# motherboard_motor_mcu.net
KiCad netlist of a schematic drawn in Altium Designer
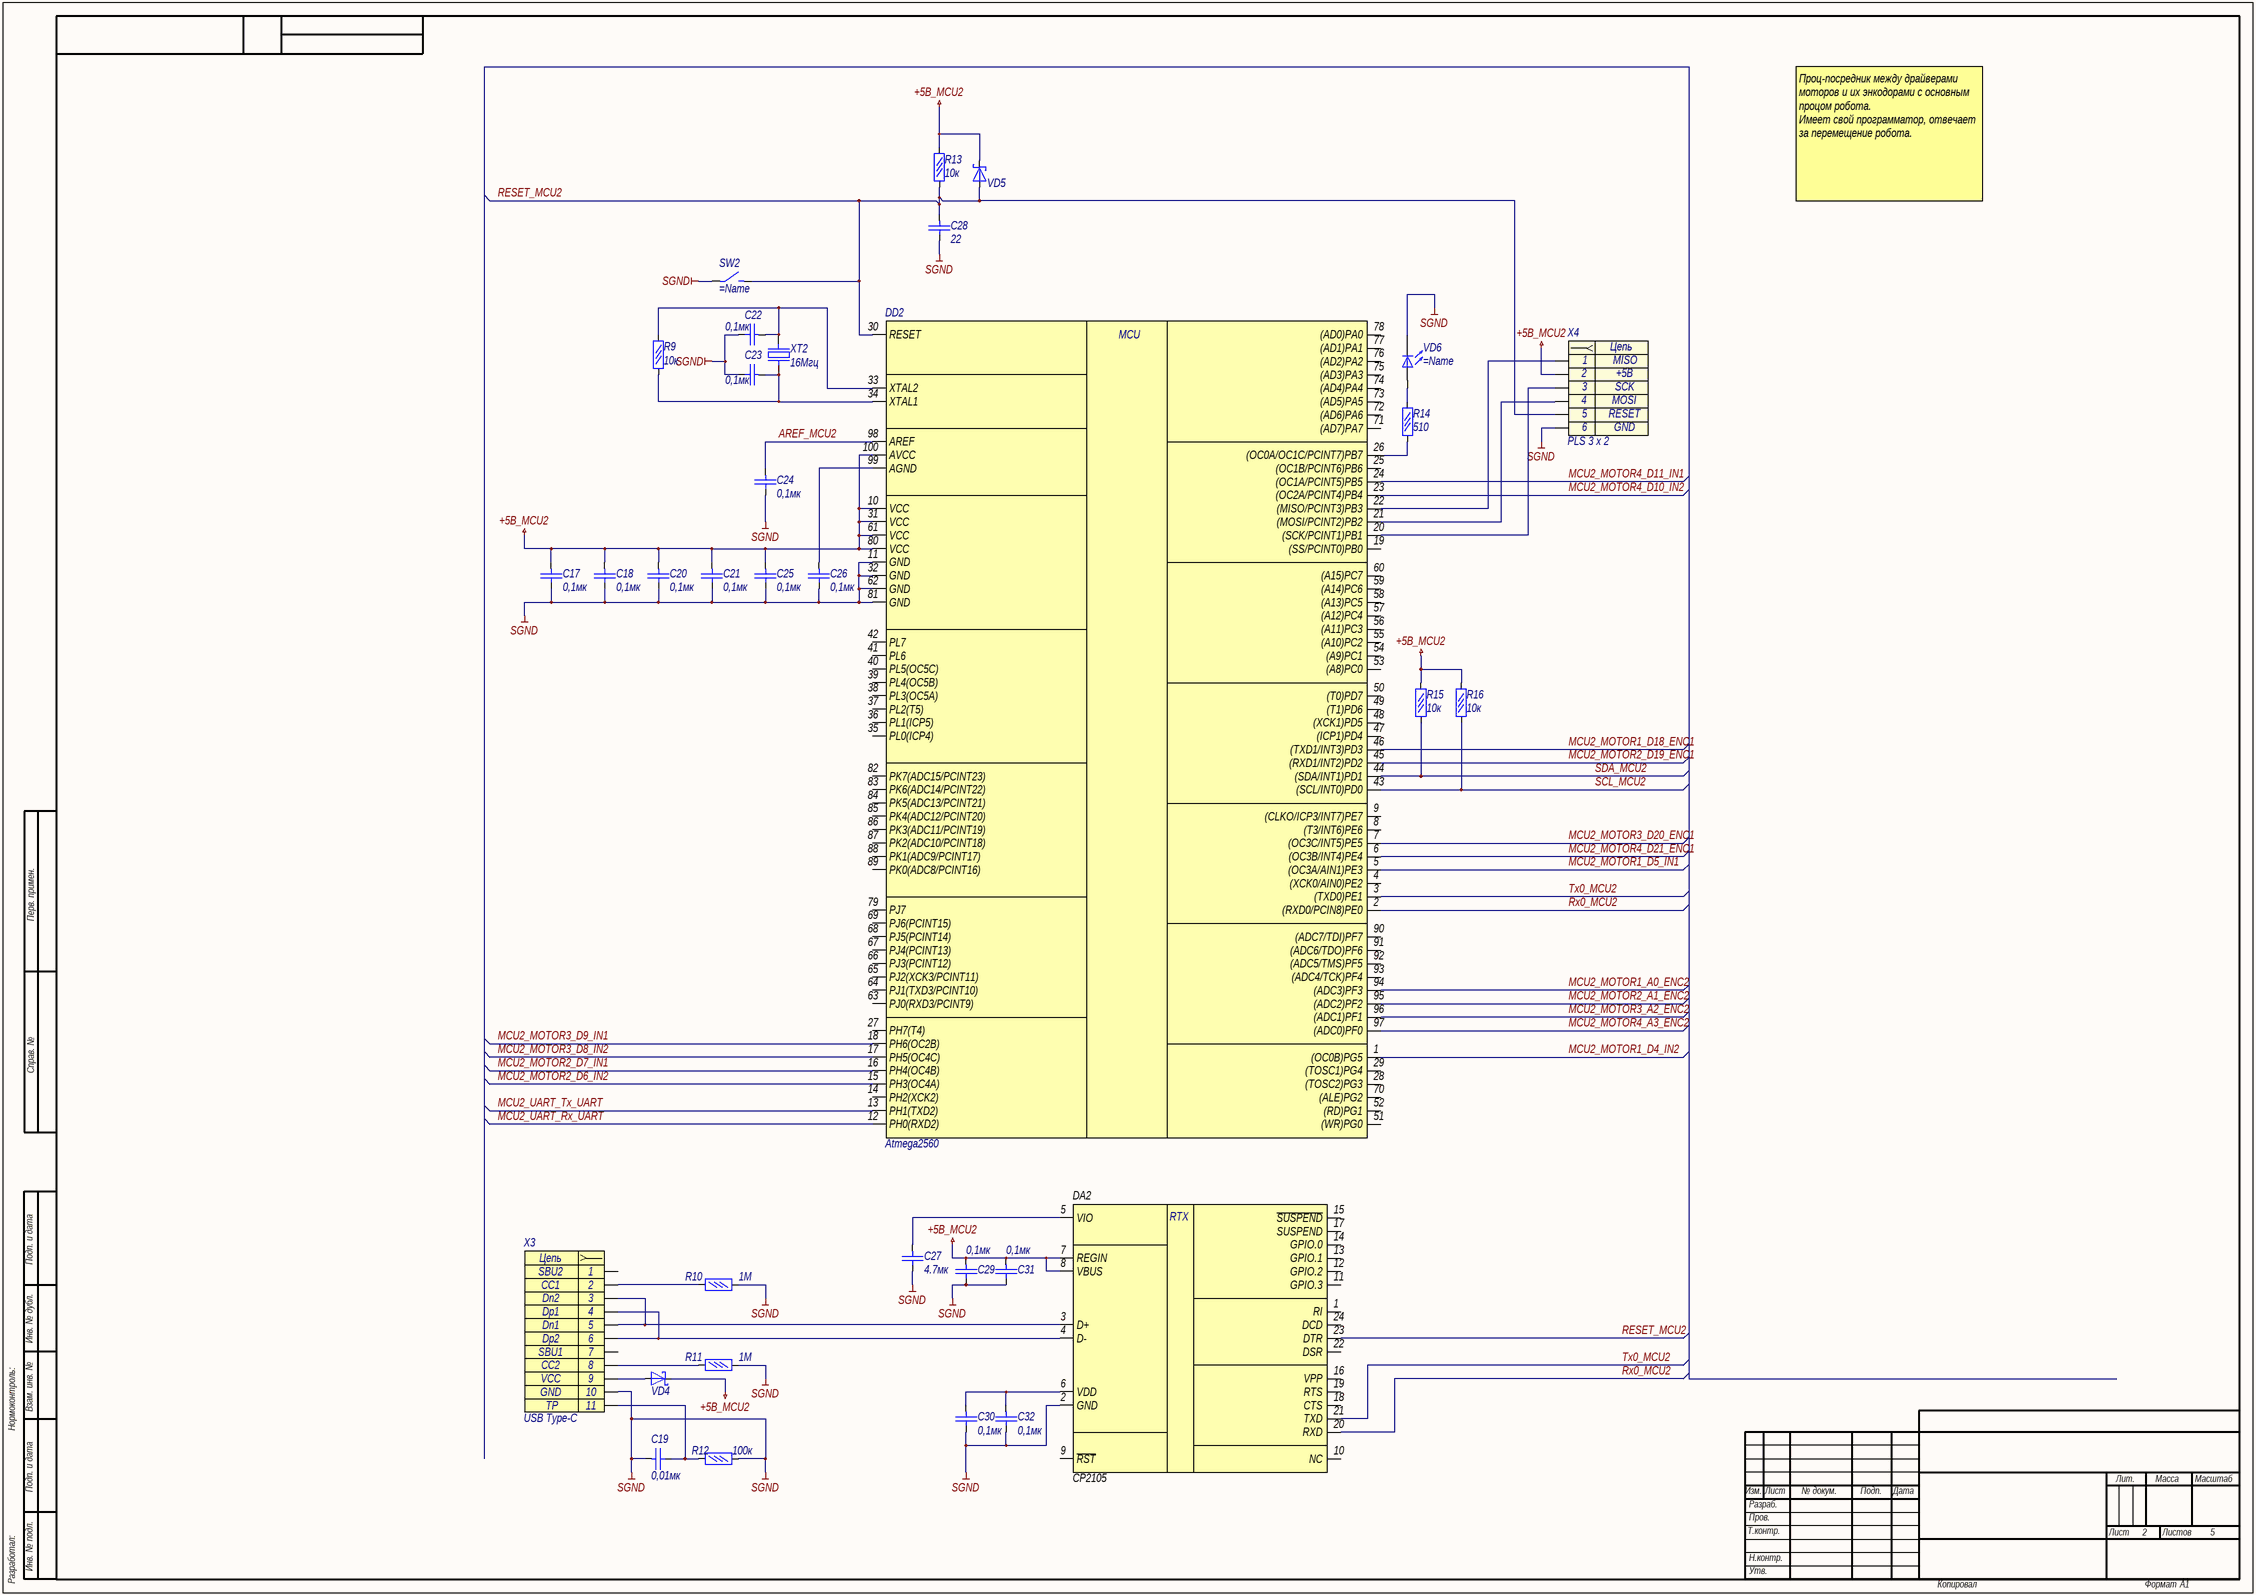
[diagram p0: motherboard_motor_mcu.SchDoc]

(export (version "E")
  (design (tool "Eeschema 10.0.6"))
  (components
    (comp (ref "DA2") (value "CP2105") (footprint "QFN24-PAD") (libsource (lib "mylib") (part "CP2104")))
    (comp (ref "DD2") (value "Atmega2560") (footprint "100A") (libsource (lib "mylib") (part "Anmega_2560")))
    (comp (ref "R9")
      (value "10к")
      (footprint "R0603")
      (description "Резистор 0,05Вт")
      (libsource (lib "") (part "Резистор 0.05Вт_2"))
    )
    (comp (ref "R10")
      (value "1М")
      (footprint "R0603")
      (description "Резистор 0,05Вт")
      (libsource (lib "mylib") (part "Резистор 0.05Вт"))
    )
    (comp (ref "R11")
      (value "1М")
      (footprint "R0603")
      (description "Резистор 0,05Вт")
      (libsource (lib "mylib") (part "Резистор 0.05Вт"))
    )
    (comp (ref "R12")
      (value "100к")
      (footprint "R0603")
      (description "Резистор 0,05Вт")
      (libsource (lib "mylib") (part "Резистор 0.05Вт"))
    )
    (comp (ref "R13")
      (value "10к")
      (footprint "R0603")
      (description "Резистор 0,05Вт")
      (libsource (lib "") (part "Резистор 0.05Вт_2"))
    )
    (comp (ref "R14")
      (value "510")
      (footprint "R0603")
      (description "Резистор 0,05Вт")
      (libsource (lib "") (part "Резистор 0.05Вт_1"))
    )
    (comp (ref "R15")
      (value "10к")
      (footprint "R0603")
      (description "Резистор 0,05Вт")
      (libsource (lib "") (part "Резистор 0.05Вт_1"))
    )
    (comp (ref "R16")
      (value "10к")
      (footprint "R0603")
      (description "Резистор 0,05Вт")
      (libsource (lib "") (part "Резистор 0.05Вт_1"))
    )
    (comp (ref "SW2") (value "~") (footprint "it-1187") (libsource (lib "mylib") (part "button")))
    (comp (ref "VD4")
      (value "~")
      (footprint "SOD123_A")
      (description "Диод Шоттки")
      (libsource (lib "mylib") (part "DiodeSchottky"))
    )
    (comp (ref "VD5")
      (value "~")
      (footprint "SOD123_A")
      (description "Диод Шоттки")
      (libsource (lib "mylib") (part "DiodeSchottky"))
    )
    (comp (ref "VD6")
      (value "~")
      (footprint "0603 - led")
      (description "smd led")
      (libsource (lib "mylib") (part "smd_led"))
    )
    (comp (ref "X3")
      (value "USB Type-C")
      (footprint "USB4105-15-A-120")
      (description "USB Type-C USB4105-GF-A / GCT")
      (libsource (lib "mylib") (part "USB4105"))
    )
    (comp (ref "X4") (value "PLS 3 x 2") (footprint "PLS 3 x 2") (libsource (lib "mylib") (part "PLS 3 x 2")))
    (comp (ref "XT2")
      (value "16Мгц")
      (footprint "KX-7")
      (description "12.88605 / Geyer")
      (libsource (lib "mylib") (part "Резонатор"))
    )
    (comp (ref "С17") (value "0,1мк") (footprint "C0402") (libsource (lib "mylib") (part "Кер. конденсатор")))
    (comp (ref "С18") (value "0,1мк") (footprint "C0402") (libsource (lib "mylib") (part "Кер. конденсатор")))
    (comp (ref "С19")
      (value "0,01мк")
      (footprint "C0603")
      (libsource (lib "mylib") (part "Кер. конденсатор"))
    )
    (comp (ref "С20") (value "0,1мк") (footprint "C0402") (libsource (lib "mylib") (part "Кер. конденсатор")))
    (comp (ref "С21") (value "0,1мк") (footprint "C0402") (libsource (lib "mylib") (part "Кер. конденсатор")))
    (comp (ref "С22") (value "0,1мк") (footprint "C0402") (libsource (lib "mylib") (part "Кер. конденсатор")))
    (comp (ref "С23") (value "0,1мк") (footprint "C0402") (libsource (lib "mylib") (part "Кер. конденсатор")))
    (comp (ref "С24") (value "0,1мк") (footprint "C0402") (libsource (lib "mylib") (part "Кер. конденсатор")))
    (comp (ref "С25") (value "0,1мк") (footprint "C0402") (libsource (lib "mylib") (part "Кер. конденсатор")))
    (comp (ref "С26") (value "0,1мк") (footprint "C0402") (libsource (lib "mylib") (part "Кер. конденсатор")))
    (comp (ref "С27") (value "4.7мк") (footprint "C0603") (libsource (lib "mylib") (part "Кер. конденсатор")))
    (comp (ref "С28") (value "22") (footprint "C0603") (libsource (lib "mylib") (part "Кер. конденсатор")))
    (comp (ref "С29") (value "0,1мк") (footprint "C0603") (libsource (lib "mylib") (part "Кер. конденсатор")))
    (comp (ref "С30") (value "0,1мк") (footprint "C0603") (libsource (lib "mylib") (part "Кер. конденсатор")))
    (comp (ref "С31") (value "0,1мк") (footprint "C0603") (libsource (lib "mylib") (part "Кер. конденсатор")))
    (comp (ref "С32") (value "0,1мк") (footprint "C0603") (libsource (lib "mylib") (part "Кер. конденсатор")))
  )
  (nets
    (net (code "1") (name "+5В_MCU2") (class "Default")
      (node (ref "DA2") (pin "7") (pinfunction "REGIN_7") (pintype "passive"))
      (node (ref "DA2") (pin "8") (pinfunction "VBUS_8") (pintype "passive"))
      (node (ref "DD2") (pin "10") (pinfunction "VCC_10") (pintype "passive"))
      (node (ref "DD2") (pin "100") (pinfunction "AVCC_100") (pintype "passive"))
      (node (ref "DD2") (pin "31") (pinfunction "VCC_31") (pintype "passive"))
      (node (ref "DD2") (pin "61") (pinfunction "VCC_61") (pintype "passive"))
      (node (ref "DD2") (pin "80") (pinfunction "VCC_80") (pintype "passive"))
      (node (ref "R13") (pin "2") (pinfunction "2_2") (pintype "passive"))
      (node (ref "R15") (pin "1") (pinfunction "1_1") (pintype "passive"))
      (node (ref "R16") (pin "1") (pinfunction "1_1") (pintype "passive"))
      (node (ref "VD4") (pin "1") (pinfunction "K_1") (pintype "passive"))
      (node (ref "VD5") (pin "1") (pinfunction "K_1") (pintype "passive"))
      (node (ref "X4") (pin "2") (pinfunction "2_2") (pintype "passive"))
      (node (ref "С17") (pin "2") (pinfunction "2_2") (pintype "passive"))
      (node (ref "С18") (pin "2") (pinfunction "2_2") (pintype "passive"))
      (node (ref "С20") (pin "2") (pinfunction "2_2") (pintype "passive"))
      (node (ref "С21") (pin "2") (pinfunction "2_2") (pintype "passive"))
      (node (ref "С25") (pin "2") (pinfunction "2_2") (pintype "passive"))
      (node (ref "С29") (pin "2") (pinfunction "2_2") (pintype "passive"))
      (node (ref "С31") (pin "2") (pinfunction "2_2") (pintype "passive"))
    )
    (net (code "2") (name "/AREF_MCU2") (class "Default")
      (node (ref "DD2") (pin "98") (pinfunction "AREF_98") (pintype "passive"))
      (node (ref "С24") (pin "2") (pinfunction "2_2") (pintype "passive"))
    )
    (net (code "3") (name "/MCU2_MOTOR1_A0_ENC2") (class "Default")
      (node (ref "DD2") (pin "94") (pinfunction "(ADC3)PF3_94") (pintype "passive"))
    )
    (net (code "4") (name "/MCU2_MOTOR1_D4_IN2") (class "Default")
      (node (ref "DD2") (pin "1") (pinfunction "(OC0B)PG5_1") (pintype "passive"))
    )
    (net (code "5") (name "/MCU2_MOTOR1_D5_IN1") (class "Default")
      (node (ref "DD2") (pin "5") (pinfunction "(OC3A/AIN1)PE3_5") (pintype "passive"))
    )
    (net (code "6") (name "/MCU2_MOTOR1_D18_ENC1") (class "Default")
      (node (ref "DD2") (pin "46") (pinfunction "(TXD1/INT3)PD3_46") (pintype "passive"))
    )
    (net (code "7") (name "/MCU2_MOTOR2_A1_ENC2") (class "Default")
      (node (ref "DD2") (pin "95") (pinfunction "(ADC2)PF2_95") (pintype "passive"))
    )
    (net (code "8") (name "/MCU2_MOTOR2_D6_IN2") (class "Default")
      (node (ref "DD2") (pin "15") (pinfunction "PH3(OC4A)_15") (pintype "passive"))
    )
    (net (code "9") (name "/MCU2_MOTOR2_D7_IN1") (class "Default")
      (node (ref "DD2") (pin "16") (pinfunction "PH4(OC4B)_16") (pintype "passive"))
    )
    (net (code "10") (name "/MCU2_MOTOR2_D19_ENC1") (class "Default")
      (node (ref "DD2") (pin "45") (pinfunction "(RXD1/INT2)PD2_45") (pintype "passive"))
    )
    (net (code "11") (name "/MCU2_MOTOR3_A2_ENC2") (class "Default")
      (node (ref "DD2") (pin "96") (pinfunction "(ADC1)PF1_96") (pintype "passive"))
    )
    (net (code "12") (name "/MCU2_MOTOR3_D8_IN2") (class "Default")
      (node (ref "DD2") (pin "17") (pinfunction "PH5(OC4C)_17") (pintype "passive"))
    )
    (net (code "13") (name "/MCU2_MOTOR3_D9_IN1") (class "Default")
      (node (ref "DD2") (pin "18") (pinfunction "PH6(OC2B)_18") (pintype "passive"))
    )
    (net (code "14") (name "/MCU2_MOTOR3_D20_ENC1") (class "Default")
      (node (ref "DD2") (pin "7") (pinfunction "(OC3C/INT5)PE5_7") (pintype "passive"))
    )
    (net (code "15") (name "/MCU2_MOTOR4_A3_ENC2") (class "Default")
      (node (ref "DD2") (pin "97") (pinfunction "(ADC0)PF0_97") (pintype "passive"))
    )
    (net (code "16") (name "/MCU2_MOTOR4_D10_IN2") (class "Default")
      (node (ref "DD2") (pin "23") (pinfunction "(OC2A/PCINT4)PB4_23") (pintype "passive"))
    )
    (net (code "17") (name "/MCU2_MOTOR4_D11_IN1") (class "Default")
      (node (ref "DD2") (pin "24") (pinfunction "(OC1A/PCINT5)PB5_24") (pintype "passive"))
    )
    (net (code "18") (name "/MCU2_MOTOR4_D21_ENC1") (class "Default")
      (node (ref "DD2") (pin "6") (pinfunction "(OC3B/INT4)PE4_6") (pintype "passive"))
    )
    (net (code "19") (name "/MCU2_UART_Rx_UART") (class "Default")
      (node (ref "DD2") (pin "12") (pinfunction "PH0(RXD2)_12") (pintype "passive"))
    )
    (net (code "20") (name "/MCU2_UART_Tx_UART") (class "Default")
      (node (ref "DD2") (pin "13") (pinfunction "PH1(TXD2)_13") (pintype "passive"))
    )
    (net (code "21") (name "/RESET_MCU2") (class "Default")
      (node (ref "DA2") (pin "23") (pinfunction "DTR_23") (pintype "passive"))
      (node (ref "DD2") (pin "30") (pinfunction "RESET_30") (pintype "passive"))
      (node (ref "R13") (pin "1") (pinfunction "1_1") (pintype "passive"))
      (node (ref "SW2") (pin "2") (pinfunction "2_2") (pintype "passive"))
      (node (ref "VD5") (pin "2") (pinfunction "A_2") (pintype "passive"))
      (node (ref "X4") (pin "5") (pinfunction "5_5") (pintype "passive"))
      (node (ref "С28") (pin "2") (pinfunction "2_2") (pintype "passive"))
    )
    (net (code "22") (name "/Rx0_MCU2") (class "Default")
      (node (ref "DA2") (pin "20") (pinfunction "RXD_20") (pintype "passive"))
      (node (ref "DD2") (pin "2") (pinfunction "(RXD0/PCIN8)PE0_2") (pintype "passive"))
    )
    (net (code "23") (name "/SCL_MCU2") (class "Default")
      (node (ref "DD2") (pin "43") (pinfunction "(SCL/INT0)PD0_43") (pintype "passive"))
      (node (ref "R16") (pin "2") (pinfunction "2_2") (pintype "passive"))
    )
    (net (code "24") (name "/SDA_MCU2") (class "Default")
      (node (ref "DD2") (pin "44") (pinfunction "(SDA/INT1)PD1_44") (pintype "passive"))
      (node (ref "R15") (pin "2") (pinfunction "2_2") (pintype "passive"))
    )
    (net (code "25") (name "/Tx0_MCU2") (class "Default")
      (node (ref "DA2") (pin "21") (pinfunction "TXD_21") (pintype "passive"))
      (node (ref "DD2") (pin "3") (pinfunction "(TXD0)PE1_3") (pintype "passive"))
    )
    (net (code "26") (name "Net-(DA2-D+)") (class "Default")
      (node (ref "DA2") (pin "3") (pinfunction "D+_3") (pintype "passive"))
      (node (ref "X3") (pin "3") (pinfunction "B7_3") (pintype "passive"))
      (node (ref "X3") (pin "5") (pinfunction "A7_5") (pintype "passive"))
    )
    (net (code "27") (name "Net-(DA2-D-)") (class "Default")
      (node (ref "DA2") (pin "4") (pinfunction "D-_4") (pintype "passive"))
      (node (ref "X3") (pin "4") (pinfunction "A6_4") (pintype "passive"))
      (node (ref "X3") (pin "6") (pinfunction "B6_6") (pintype "passive"))
    )
    (net (code "28") (name "Net-(DA2-VDD)") (class "Default")
      (node (ref "DA2") (pin "6") (pinfunction "VDD_6") (pintype "passive"))
      (node (ref "С30") (pin "2") (pinfunction "2_2") (pintype "passive"))
      (node (ref "С32") (pin "2") (pinfunction "2_2") (pintype "passive"))
    )
    (net (code "29") (name "Net-(DA2-VIO)") (class "Default")
      (node (ref "DA2") (pin "5") (pinfunction "VIO_5") (pintype "passive"))
      (node (ref "С27") (pin "2") (pinfunction "2_2") (pintype "passive"))
    )
    (net (code "30") (name "Net-(DD2-(MISO{slash}PCINT3)PB3)") (class "Default")
      (node (ref "DD2") (pin "22") (pinfunction "(MISO/PCINT3)PB3_22") (pintype "passive"))
      (node (ref "X4") (pin "1") (pinfunction "1_1") (pintype "passive"))
    )
    (net (code "31") (name "Net-(DD2-(MOSI{slash}PCINT2)PB2)") (class "Default")
      (node (ref "DD2") (pin "21") (pinfunction "(MOSI/PCINT2)PB2_21") (pintype "passive"))
      (node (ref "X4") (pin "4") (pinfunction "4_4") (pintype "passive"))
    )
    (net (code "32") (name "Net-(DD2-(OC0A{slash}OC1C{slash}PCINT7)PB7)") (class "Default")
      (node (ref "DD2") (pin "26") (pinfunction "(OC0A/OC1C/PCINT7)PB7_26") (pintype "passive"))
      (node (ref "R14") (pin "2") (pinfunction "2_2") (pintype "passive"))
    )
    (net (code "33") (name "Net-(DD2-(SCK{slash}PCINT1)PB1)") (class "Default")
      (node (ref "DD2") (pin "20") (pinfunction "(SCK/PCINT1)PB1_20") (pintype "passive"))
      (node (ref "X4") (pin "3") (pinfunction "3_3") (pintype "passive"))
    )
    (net (code "34") (name "Net-(DD2-AGND)") (class "Default")
      (node (ref "DD2") (pin "99") (pinfunction "AGND_99") (pintype "passive"))
      (node (ref "С26") (pin "2") (pinfunction "2_2") (pintype "passive"))
    )
    (net (code "35") (name "Net-(DD2-XTAL1)") (class "Default")
      (node (ref "DD2") (pin "34") (pinfunction "XTAL1_34") (pintype "passive"))
      (node (ref "R9") (pin "1") (pinfunction "1_1") (pintype "passive"))
      (node (ref "XT2") (pin "1") (pinfunction "1_1") (pintype "passive"))
      (node (ref "С23") (pin "2") (pinfunction "2_2") (pintype "passive"))
    )
    (net (code "36") (name "Net-(DD2-XTAL2)") (class "Default")
      (node (ref "DD2") (pin "33") (pinfunction "XTAL2_33") (pintype "passive"))
      (node (ref "R9") (pin "2") (pinfunction "2_2") (pintype "passive"))
      (node (ref "XT2") (pin "3") (pinfunction "3_3") (pintype "passive"))
      (node (ref "С22") (pin "2") (pinfunction "2_2") (pintype "passive"))
    )
    (net (code "37") (name "Net-(R12-Pad1)") (class "Default")
      (node (ref "R12") (pin "1") (pinfunction "1_1") (pintype "passive"))
      (node (ref "X3") (pin "TP") (pinfunction "TP_TP") (pintype "passive"))
      (node (ref "С19") (pin "1") (pinfunction "1_1") (pintype "passive"))
    )
    (net (code "38") (name "Net-(VD4-A)") (class "Default")
      (node (ref "VD4") (pin "2") (pinfunction "A_2") (pintype "passive"))
      (node (ref "X3") (pin "9") (pinfunction "GND_9") (pintype "passive"))
    )
    (net (code "39") (name "Net-(VD6-A)") (class "Default")
      (node (ref "R14") (pin "1") (pinfunction "1_1") (pintype "passive"))
      (node (ref "VD6") (pin "1") (pinfunction "A_1") (pintype "passive"))
    )
    (net (code "40") (name "Net-(X3-A5)") (class "Default")
      (node (ref "R10") (pin "1") (pinfunction "1_1") (pintype "passive"))
      (node (ref "X3") (pin "2") (pinfunction "A5_2") (pintype "passive"))
    )
    (net (code "41") (name "Net-(X3-B5)") (class "Default")
      (node (ref "R11") (pin "1") (pinfunction "1_1") (pintype "passive"))
      (node (ref "X3") (pin "8") (pinfunction "B5_8") (pintype "passive"))
    )
    (net (code "42") (name "SGND") (class "Default")
      (node (ref "DA2") (pin "2") (pinfunction "GND_2") (pintype "passive"))
      (node (ref "DD2") (pin "11") (pinfunction "GND_11") (pintype "passive"))
      (node (ref "DD2") (pin "32") (pinfunction "GND_32") (pintype "passive"))
      (node (ref "DD2") (pin "62") (pinfunction "GND_62") (pintype "passive"))
      (node (ref "DD2") (pin "81") (pinfunction "GND_81") (pintype "passive"))
      (node (ref "R10") (pin "2") (pinfunction "2_2") (pintype "passive"))
      (node (ref "R11") (pin "2") (pinfunction "2_2") (pintype "passive"))
      (node (ref "R12") (pin "2") (pinfunction "2_2") (pintype "passive"))
      (node (ref "SW2") (pin "1") (pinfunction "1_1") (pintype "passive"))
      (node (ref "VD6") (pin "2") (pinfunction "K_2") (pintype "passive"))
      (node (ref "X3") (pin "10") (pinfunction "VCC_10") (pintype "passive"))
      (node (ref "X4") (pin "6") (pinfunction "6_6") (pintype "passive"))
      (node (ref "С17") (pin "1") (pinfunction "1_1") (pintype "passive"))
      (node (ref "С18") (pin "1") (pinfunction "1_1") (pintype "passive"))
      (node (ref "С19") (pin "2") (pinfunction "2_2") (pintype "passive"))
      (node (ref "С20") (pin "1") (pinfunction "1_1") (pintype "passive"))
      (node (ref "С21") (pin "1") (pinfunction "1_1") (pintype "passive"))
      (node (ref "С22") (pin "1") (pinfunction "1_1") (pintype "passive"))
      (node (ref "С23") (pin "1") (pinfunction "1_1") (pintype "passive"))
      (node (ref "С24") (pin "1") (pinfunction "1_1") (pintype "passive"))
      (node (ref "С25") (pin "1") (pinfunction "1_1") (pintype "passive"))
      (node (ref "С26") (pin "1") (pinfunction "1_1") (pintype "passive"))
      (node (ref "С27") (pin "1") (pinfunction "1_1") (pintype "passive"))
      (node (ref "С28") (pin "1") (pinfunction "1_1") (pintype "passive"))
      (node (ref "С29") (pin "1") (pinfunction "1_1") (pintype "passive"))
      (node (ref "С30") (pin "1") (pinfunction "1_1") (pintype "passive"))
      (node (ref "С31") (pin "1") (pinfunction "1_1") (pintype "passive"))
      (node (ref "С32") (pin "1") (pinfunction "1_1") (pintype "passive"))
    )
    (net (code "43") (name "unconnected-(DA2-CTS-Pad18)") (class "Default")
      (node (ref "DA2") (pin "18") (pinfunction "CTS_18") (pintype "passive"))
    )
    (net (code "44") (name "unconnected-(DA2-DCD-Pad24)") (class "Default")
      (node (ref "DA2") (pin "24") (pinfunction "DCD_24") (pintype "passive"))
    )
    (net (code "45") (name "unconnected-(DA2-DSR-Pad22)") (class "Default")
      (node (ref "DA2") (pin "22") (pinfunction "DSR_22") (pintype "passive"))
    )
    (net (code "46") (name "unconnected-(DA2-GPIO.0-Pad14)") (class "Default")
      (node (ref "DA2") (pin "14") (pinfunction "GPIO.0_14") (pintype "passive"))
    )
    (net (code "47") (name "unconnected-(DA2-GPIO.1-Pad13)") (class "Default")
      (node (ref "DA2") (pin "13") (pinfunction "GPIO.1_13") (pintype "passive"))
    )
    (net (code "48") (name "unconnected-(DA2-GPIO.2-Pad12)") (class "Default")
      (node (ref "DA2") (pin "12") (pinfunction "GPIO.2_12") (pintype "passive"))
    )
    (net (code "49") (name "unconnected-(DA2-GPIO.3-Pad11)") (class "Default")
      (node (ref "DA2") (pin "11") (pinfunction "GPIO.3_11") (pintype "passive"))
    )
    (net (code "50") (name "unconnected-(DA2-NC-Pad10)") (class "Default")
      (node (ref "DA2") (pin "10") (pinfunction "NC_10") (pintype "passive"))
    )
    (net (code "51") (name "unconnected-(DA2-RI-Pad1)") (class "Default")
      (node (ref "DA2") (pin "1") (pinfunction "RI_1") (pintype "passive"))
    )
    (net (code "52") (name "unconnected-(DA2-RTS-Pad19)") (class "Default")
      (node (ref "DA2") (pin "19") (pinfunction "RTS_19") (pintype "passive"))
    )
    (net (code "53") (name "unconnected-(DA2-SUSPEND-Pad17)") (class "Default")
      (node (ref "DA2") (pin "17") (pinfunction "SUSPEND_17") (pintype "passive"))
    )
    (net (code "54") (name "unconnected-(DA2-VPP-Pad16)") (class "Default")
      (node (ref "DA2") (pin "16") (pinfunction "VPP_16") (pintype "passive"))
    )
    (net (code "55") (name "unconnected-(DA2-~{RST}-Pad9)") (class "Default")
      (node (ref "DA2") (pin "9") (pinfunction "~{RST}_9") (pintype "passive"))
    )
    (net (code "56") (name "unconnected-(DA2-~{SUSPEND}-Pad15)") (class "Default")
      (node (ref "DA2") (pin "15") (pinfunction "~{SUSPEND}_15") (pintype "passive"))
    )
    (net (code "57") (name "unconnected-(DD2-(A8)PC0-Pad53)") (class "Default")
      (node (ref "DD2") (pin "53") (pinfunction "(A8)PC0_53") (pintype "passive"))
    )
    (net (code "58") (name "unconnected-(DD2-(A9)PC1-Pad54)") (class "Default")
      (node (ref "DD2") (pin "54") (pinfunction "(A9)PC1_54") (pintype "passive"))
    )
    (net (code "59") (name "unconnected-(DD2-(A10)PC2-Pad55)") (class "Default")
      (node (ref "DD2") (pin "55") (pinfunction "(A10)PC2_55") (pintype "passive"))
    )
    (net (code "60") (name "unconnected-(DD2-(A11)PC3-Pad56)") (class "Default")
      (node (ref "DD2") (pin "56") (pinfunction "(A11)PC3_56") (pintype "passive"))
    )
    (net (code "61") (name "unconnected-(DD2-(A12)PC4-Pad57)") (class "Default")
      (node (ref "DD2") (pin "57") (pinfunction "(A12)PC4_57") (pintype "passive"))
    )
    (net (code "62") (name "unconnected-(DD2-(A13)PC5-Pad58)") (class "Default")
      (node (ref "DD2") (pin "58") (pinfunction "(A13)PC5_58") (pintype "passive"))
    )
    (net (code "63") (name "unconnected-(DD2-(A14)PC6-Pad59)") (class "Default")
      (node (ref "DD2") (pin "59") (pinfunction "(A14)PC6_59") (pintype "passive"))
    )
    (net (code "64") (name "unconnected-(DD2-(A15)PC7-Pad60)") (class "Default")
      (node (ref "DD2") (pin "60") (pinfunction "(A15)PC7_60") (pintype "passive"))
    )
    (net (code "65") (name "unconnected-(DD2-(AD0)PA0-Pad78)") (class "Default")
      (node (ref "DD2") (pin "78") (pinfunction "(AD0)PA0_78") (pintype "passive"))
    )
    (net (code "66") (name "unconnected-(DD2-(AD1)PA1-Pad77)") (class "Default")
      (node (ref "DD2") (pin "77") (pinfunction "(AD1)PA1_77") (pintype "passive"))
    )
    (net (code "67") (name "unconnected-(DD2-(AD2)PA2-Pad76)") (class "Default")
      (node (ref "DD2") (pin "76") (pinfunction "(AD2)PA2_76") (pintype "passive"))
    )
    (net (code "68") (name "unconnected-(DD2-(AD3)PA3-Pad75)") (class "Default")
      (node (ref "DD2") (pin "75") (pinfunction "(AD3)PA3_75") (pintype "passive"))
    )
    (net (code "69") (name "unconnected-(DD2-(AD4)PA4-Pad74)") (class "Default")
      (node (ref "DD2") (pin "74") (pinfunction "(AD4)PA4_74") (pintype "passive"))
    )
    (net (code "70") (name "unconnected-(DD2-(AD5)PA5-Pad73)") (class "Default")
      (node (ref "DD2") (pin "73") (pinfunction "(AD5)PA5_73") (pintype "passive"))
    )
    (net (code "71") (name "unconnected-(DD2-(AD6)PA6-Pad72)") (class "Default")
      (node (ref "DD2") (pin "72") (pinfunction "(AD6)PA6_72") (pintype "passive"))
    )
    (net (code "72") (name "unconnected-(DD2-(AD7)PA7-Pad71)") (class "Default")
      (node (ref "DD2") (pin "71") (pinfunction "(AD7)PA7_71") (pintype "passive"))
    )
    (net (code "73") (name "unconnected-(DD2-(ADC4{slash}TCK)PF4-Pad93)") (class "Default")
      (node (ref "DD2") (pin "93") (pinfunction "(ADC4/TCK)PF4_93") (pintype "passive"))
    )
    (net (code "74") (name "unconnected-(DD2-(ADC5{slash}TMS)PF5-Pad92)") (class "Default")
      (node (ref "DD2") (pin "92") (pinfunction "(ADC5/TMS)PF5_92") (pintype "passive"))
    )
    (net (code "75") (name "unconnected-(DD2-(ADC6{slash}TDO)PF6-Pad91)") (class "Default")
      (node (ref "DD2") (pin "91") (pinfunction "(ADC6/TDO)PF6_91") (pintype "passive"))
    )
    (net (code "76") (name "unconnected-(DD2-(ADC7{slash}TDI)PF7-Pad90)") (class "Default")
      (node (ref "DD2") (pin "90") (pinfunction "(ADC7/TDI)PF7_90") (pintype "passive"))
    )
    (net (code "77") (name "unconnected-(DD2-(ALE)PG2-Pad70)") (class "Default")
      (node (ref "DD2") (pin "70") (pinfunction "(ALE)PG2_70") (pintype "passive"))
    )
    (net (code "78") (name "unconnected-(DD2-(CLKO{slash}ICP3{slash}INT7)PE7-Pad9)") (class "Default")
      (node (ref "DD2") (pin "9") (pinfunction "(CLKO/ICP3/INT7)PE7_9") (pintype "passive"))
    )
    (net (code "79") (name "unconnected-(DD2-(ICP1)PD4-Pad47)") (class "Default")
      (node (ref "DD2") (pin "47") (pinfunction "(ICP1)PD4_47") (pintype "passive"))
    )
    (net (code "80") (name "unconnected-(DD2-(OC1B{slash}PCINT6)PB6-Pad25)") (class "Default")
      (node (ref "DD2") (pin "25") (pinfunction "(OC1B/PCINT6)PB6_25") (pintype "passive"))
    )
    (net (code "81") (name "unconnected-(DD2-(RD)PG1-Pad52)") (class "Default")
      (node (ref "DD2") (pin "52") (pinfunction "(RD)PG1_52") (pintype "passive"))
    )
    (net (code "82") (name "unconnected-(DD2-(SS{slash}PCINT0)PB0-Pad19)") (class "Default")
      (node (ref "DD2") (pin "19") (pinfunction "(SS/PCINT0)PB0_19") (pintype "passive"))
    )
    (net (code "83") (name "unconnected-(DD2-(T0)PD7-Pad50)") (class "Default")
      (node (ref "DD2") (pin "50") (pinfunction "(T0)PD7_50") (pintype "passive"))
    )
    (net (code "84") (name "unconnected-(DD2-(T1)PD6-Pad49)") (class "Default")
      (node (ref "DD2") (pin "49") (pinfunction "(T1)PD6_49") (pintype "passive"))
    )
    (net (code "85") (name "unconnected-(DD2-(T3{slash}INT6)PE6-Pad8)") (class "Default")
      (node (ref "DD2") (pin "8") (pinfunction "(T3/INT6)PE6_8") (pintype "passive"))
    )
    (net (code "86") (name "unconnected-(DD2-(TOSC1)PG4-Pad29)") (class "Default")
      (node (ref "DD2") (pin "29") (pinfunction "(TOSC1)PG4_29") (pintype "passive"))
    )
    (net (code "87") (name "unconnected-(DD2-(TOSC2)PG3-Pad28)") (class "Default")
      (node (ref "DD2") (pin "28") (pinfunction "(TOSC2)PG3_28") (pintype "passive"))
    )
    (net (code "88") (name "unconnected-(DD2-(WR)PG0-Pad51)") (class "Default")
      (node (ref "DD2") (pin "51") (pinfunction "(WR)PG0_51") (pintype "passive"))
    )
    (net (code "89") (name "unconnected-(DD2-(XCK0{slash}AIN0)PE2-Pad4)") (class "Default")
      (node (ref "DD2") (pin "4") (pinfunction "(XCK0/AIN0)PE2_4") (pintype "passive"))
    )
    (net (code "90") (name "unconnected-(DD2-(XCK1)PD5-Pad48)") (class "Default")
      (node (ref "DD2") (pin "48") (pinfunction "(XCK1)PD5_48") (pintype "passive"))
    )
    (net (code "91") (name "unconnected-(DD2-PH2(XCK2)-Pad14)") (class "Default")
      (node (ref "DD2") (pin "14") (pinfunction "PH2(XCK2)_14") (pintype "passive"))
    )
    (net (code "92") (name "unconnected-(DD2-PH7(T4)-Pad27)") (class "Default")
      (node (ref "DD2") (pin "27") (pinfunction "PH7(T4)_27") (pintype "passive"))
    )
    (net (code "93") (name "unconnected-(DD2-PJ0(RXD3{slash}PCINT9)-Pad63)") (class "Default")
      (node (ref "DD2") (pin "63") (pinfunction "PJ0(RXD3/PCINT9)_63") (pintype "passive"))
    )
    (net (code "94") (name "unconnected-(DD2-PJ1(TXD3{slash}PCINT10)-Pad64)") (class "Default")
      (node (ref "DD2") (pin "64") (pinfunction "PJ1(TXD3/PCINT10)_64") (pintype "passive"))
    )
    (net (code "95") (name "unconnected-(DD2-PJ2(XCK3{slash}PCINT11)-Pad65)") (class "Default")
      (node (ref "DD2") (pin "65") (pinfunction "PJ2(XCK3/PCINT11)_65") (pintype "passive"))
    )
    (net (code "96") (name "unconnected-(DD2-PJ3(PCINT12)-Pad66)") (class "Default")
      (node (ref "DD2") (pin "66") (pinfunction "PJ3(PCINT12)_66") (pintype "passive"))
    )
    (net (code "97") (name "unconnected-(DD2-PJ4(PCINT13)-Pad67)") (class "Default")
      (node (ref "DD2") (pin "67") (pinfunction "PJ4(PCINT13)_67") (pintype "passive"))
    )
    (net (code "98") (name "unconnected-(DD2-PJ5(PCINT14)-Pad68)") (class "Default")
      (node (ref "DD2") (pin "68") (pinfunction "PJ5(PCINT14)_68") (pintype "passive"))
    )
    (net (code "99") (name "unconnected-(DD2-PJ6(PCINT15)-Pad69)") (class "Default")
      (node (ref "DD2") (pin "69") (pinfunction "PJ6(PCINT15)_69") (pintype "passive"))
    )
    (net (code "100") (name "unconnected-(DD2-PJ7-Pad79)") (class "Default")
      (node (ref "DD2") (pin "79") (pinfunction "PJ7_79") (pintype "passive"))
    )
    (net (code "101") (name "unconnected-(DD2-PK0(ADC8{slash}PCINT16)-Pad89)") (class "Default")
      (node (ref "DD2") (pin "89") (pinfunction "PK0(ADC8/PCINT16)_89") (pintype "passive"))
    )
    (net (code "102") (name "unconnected-(DD2-PK1(ADC9{slash}PCINT17)-Pad88)") (class "Default")
      (node (ref "DD2") (pin "88") (pinfunction "PK1(ADC9/PCINT17)_88") (pintype "passive"))
    )
    (net (code "103") (name "unconnected-(DD2-PK2(ADC10{slash}PCINT18)-Pad87)") (class "Default")
      (node (ref "DD2") (pin "87") (pinfunction "PK2(ADC10/PCINT18)_87") (pintype "passive"))
    )
    (net (code "104") (name "unconnected-(DD2-PK3(ADC11{slash}PCINT19)-Pad86)") (class "Default")
      (node (ref "DD2") (pin "86") (pinfunction "PK3(ADC11/PCINT19)_86") (pintype "passive"))
    )
    (net (code "105") (name "unconnected-(DD2-PK4(ADC12{slash}PCINT20)-Pad85)") (class "Default")
      (node (ref "DD2") (pin "85") (pinfunction "PK4(ADC12/PCINT20)_85") (pintype "passive"))
    )
    (net (code "106") (name "unconnected-(DD2-PK5(ADC13{slash}PCINT21)-Pad84)") (class "Default")
      (node (ref "DD2") (pin "84") (pinfunction "PK5(ADC13/PCINT21)_84") (pintype "passive"))
    )
    (net (code "107") (name "unconnected-(DD2-PK6(ADC14{slash}PCINT22)-Pad83)") (class "Default")
      (node (ref "DD2") (pin "83") (pinfunction "PK6(ADC14/PCINT22)_83") (pintype "passive"))
    )
    (net (code "108") (name "unconnected-(DD2-PK7(ADC15{slash}PCINT23)-Pad82)") (class "Default")
      (node (ref "DD2") (pin "82") (pinfunction "PK7(ADC15/PCINT23)_82") (pintype "passive"))
    )
    (net (code "109") (name "unconnected-(DD2-PL0(ICP4)-Pad35)") (class "Default")
      (node (ref "DD2") (pin "35") (pinfunction "PL0(ICP4)_35") (pintype "passive"))
    )
    (net (code "110") (name "unconnected-(DD2-PL1(ICP5)-Pad36)") (class "Default")
      (node (ref "DD2") (pin "36") (pinfunction "PL1(ICP5)_36") (pintype "passive"))
    )
    (net (code "111") (name "unconnected-(DD2-PL2(T5)-Pad37)") (class "Default")
      (node (ref "DD2") (pin "37") (pinfunction "PL2(T5)_37") (pintype "passive"))
    )
    (net (code "112") (name "unconnected-(DD2-PL3(OC5A)-Pad38)") (class "Default")
      (node (ref "DD2") (pin "38") (pinfunction "PL3(OC5A)_38") (pintype "passive"))
    )
    (net (code "113") (name "unconnected-(DD2-PL4(OC5B)-Pad39)") (class "Default")
      (node (ref "DD2") (pin "39") (pinfunction "PL4(OC5B)_39") (pintype "passive"))
    )
    (net (code "114") (name "unconnected-(DD2-PL5(OC5C)-Pad40)") (class "Default")
      (node (ref "DD2") (pin "40") (pinfunction "PL5(OC5C)_40") (pintype "passive"))
    )
    (net (code "115") (name "unconnected-(DD2-PL6-Pad41)") (class "Default")
      (node (ref "DD2") (pin "41") (pinfunction "PL6_41") (pintype "passive"))
    )
    (net (code "116") (name "unconnected-(DD2-PL7-Pad42)") (class "Default")
      (node (ref "DD2") (pin "42") (pinfunction "PL7_42") (pintype "passive"))
    )
    (net (code "117") (name "unconnected-(X3-A8-Pad7)") (class "Default")
      (node (ref "X3") (pin "7") (pinfunction "A8_7") (pintype "passive"))
    )
    (net (code "118") (name "unconnected-(X3-B8-Pad1)") (class "Default")
      (node (ref "X3") (pin "1") (pinfunction "B8_1") (pintype "passive"))
    )
  )
)
